# AWR2243_LC_Filtering.net
KiCad netlist of a schematic drawn in Altium Designer
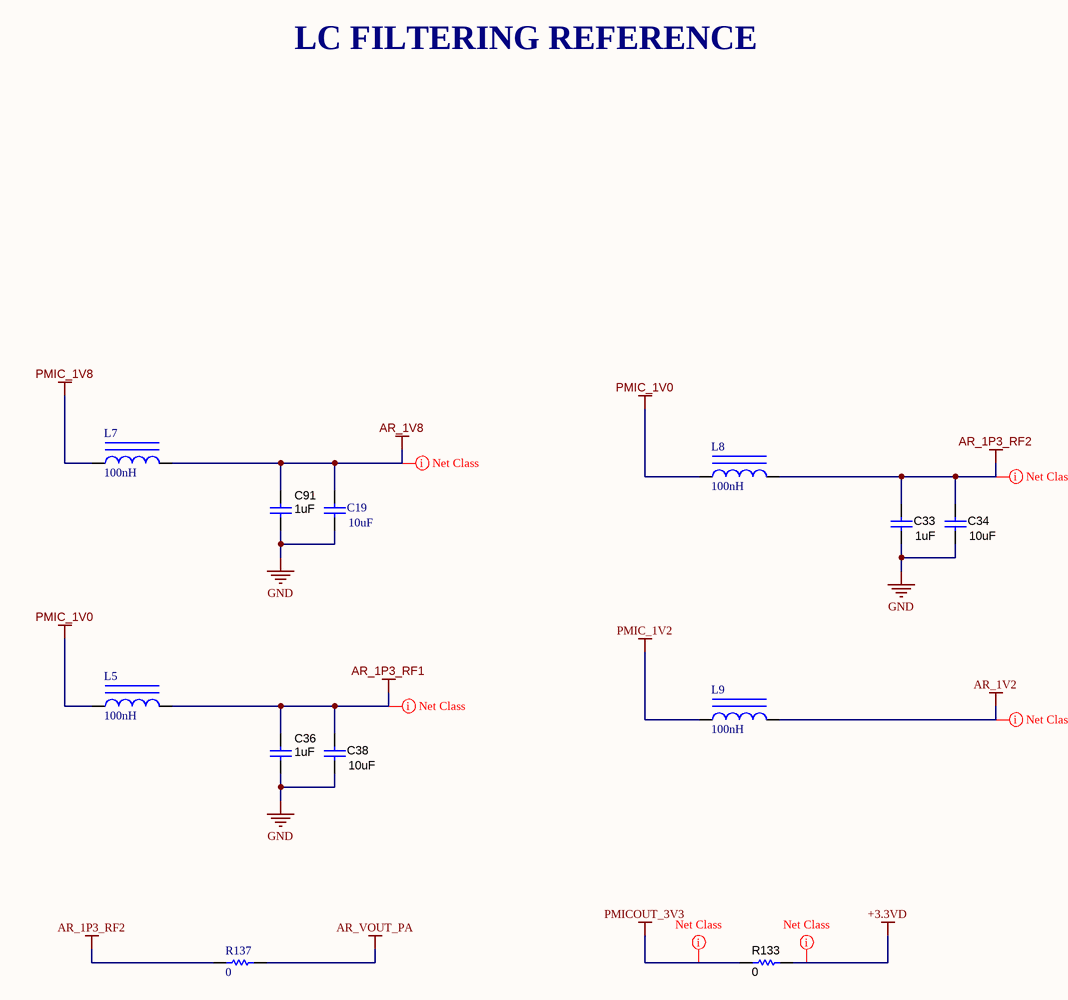
[diagram p0: AWR2243_LC_Filtering.SchDoc]

(export (version "E")
  (design (tool "Eeschema 10.0.6"))
  (components
    (comp (ref "C19")
      (value "GCM21BR71A106KE22L")
      (footprint "0805_HV")
      (description "CAP, CERM, 10 uF, 10 V, +/- 10%, X7R, 0805")
      (fields
        (field (name "MANUFACTURER") "MuRata")
        (field (name "VALUEDISPLAYED") "10uF")
        (field (name "PUBLISHER") "Texas Instruments")
      )
      (libsource (lib "Altium Vault - TI") (part "Capacitor"))
    )
    (comp (ref "C33")
      (value "GCM188R71C105KA64D")
      (footprint "0603")
      (description "CAP, CERM, 1 uF, 16 V, +/- 10%, X7R, AEC-Q200 Grade 1, 0603")
      (fields
        (field (name "MANUFACTURER") "MuRata")
        (field (name "VALUEDISPLAYED") "1uF")
        (field (name "PUBLISHER") "Texas Instruments")
      )
      (libsource (lib "Altium Vault - TI") (part "Capacitor"))
    )
    (comp (ref "C34")
      (value "GCM21BR71A106KE22L")
      (footprint "0805_HV")
      (description "CAP, CERM, 10 uF, 10 V, +/- 10%, X7R, 0805")
      (fields
        (field (name "MANUFACTURER") "MuRata")
        (field (name "VALUEDISPLAYED") "10uF")
        (field (name "PUBLISHER") "Texas Instruments")
      )
      (libsource (lib "Altium Vault - TI") (part "CMP-0008017-2"))
    )
    (comp (ref "C36")
      (value "GCM188R71C105KA64D")
      (footprint "0603")
      (description "CAP, CERM, 1 uF, 16 V, +/- 10%, X7R, AEC-Q200 Grade 1, 0603")
      (fields
        (field (name "MANUFACTURER") "MuRata")
        (field (name "VALUEDISPLAYED") "1uF")
        (field (name "PUBLISHER") "Texas Instruments")
      )
      (libsource (lib "Altium Vault - TI") (part "Capacitor"))
    )
    (comp (ref "C38")
      (value "GCM21BR71A106KE22L")
      (footprint "0805_HV")
      (description "CAP, CERM, 10 uF, 10 V, +/- 10%, X7R, 0805")
      (fields
        (field (name "MANUFACTURER") "MuRata")
        (field (name "VALUEDISPLAYED") "10uF")
        (field (name "PUBLISHER") "Texas Instruments")
      )
      (libsource (lib "Altium Vault - TI") (part "CMP-0008017-2"))
    )
    (comp (ref "C91")
      (value "GCM188R71C105KA64D")
      (footprint "0603")
      (description "CAP, CERM, 1 uF, 16 V, +/- 10%, X7R, AEC-Q200 Grade 1, 0603")
      (fields
        (field (name "MANUFACTURER") "MuRata")
        (field (name "VALUEDISPLAYED") "1uF")
        (field (name "PUBLISHER") "Texas Instruments")
      )
      (libsource (lib "Altium Vault - TI") (part "Capacitor"))
    )
    (comp (ref "L5")
      (value "NLCV32T-R10M-EFRD")
      (footprint "NLCV32")
      (description "Inductor, Wirewound, Ferrite, 100 nH, 2.85 A, 0.024 ohm, AEC-Q200 Grade 1, SMD")
      (fields (field (name "MANUFACTURER") "TDK") (field (name "VALUEDISPLAYED") "100nH"))
      (libsource (lib "Altium Vault - TI") (part "Inductor_Iron"))
    )
    (comp (ref "L7")
      (value "NLCV32T-R10M-EFRD")
      (footprint "NLCV32")
      (description "Inductor, Wirewound, Ferrite, 100 nH, 2.85 A, 0.024 ohm, AEC-Q200 Grade 1, SMD")
      (fields (field (name "MANUFACTURER") "TDK") (field (name "VALUEDISPLAYED") "100nH"))
      (libsource (lib "Altium Vault - TI") (part "Inductor_Iron"))
    )
    (comp (ref "L8")
      (value "NLCV32T-R10M-EFRD")
      (footprint "NLCV32")
      (description "Inductor, Wirewound, Ferrite, 100 nH, 2.85 A, 0.024 ohm, AEC-Q200 Grade 1, SMD")
      (fields (field (name "MANUFACTURER") "TDK") (field (name "VALUEDISPLAYED") "100nH"))
      (libsource (lib "Altium Vault - TI") (part "Inductor_Iron"))
    )
    (comp (ref "L9")
      (value "NLCV32T-R10M-EFRD")
      (footprint "NLCV32")
      (description "Inductor, Wirewound, Ferrite, 100 nH, 2.85 A, 0.024 ohm, AEC-Q200 Grade 1, SMD")
      (fields (field (name "MANUFACTURER") "TDK") (field (name "VALUEDISPLAYED") "100nH"))
      (libsource (lib "Altium Vault - TI") (part "Inductor_Iron"))
    )
    (comp (ref "R133")
      (value "MCT06030Z0000ZP500")
      (footprint "0603")
      (description "RES, 0, 5%, 0.125 W, 0603")
      (fields
        (field (name "MANUFACTURER") "Vishay/Beyschlag")
        (field (name "VALUEDISPLAYED") "0")
        (field (name "PUBLISHER") "Texas Instruments")
      )
      (libsource (lib "Altium Vault - TI") (part "Resistor"))
    )
    (comp (ref "R137")
      (value "MCT06030Z0000ZP500")
      (footprint "0603")
      (description "RES, 0, 5%, 0.125 W, 0603")
      (fields
        (field (name "MANUFACTURER") "Vishay/Beyschlag")
        (field (name "VALUEDISPLAYED") "0")
        (field (name "PUBLISHER") "Texas Instruments")
      )
      (libsource (lib "Altium Vault - TI") (part "CMP-0025884-3"))
    )
  )
  (nets
    (net (code "1") (name "+3.3VD") (class "Default")
      (node (ref "R133") (pin "2") (pinfunction "2_2") (pintype "passive"))
    )
    (net (code "2") (name "AR_1P3_RF1") (class "Default")
      (node (ref "C36") (pin "2") (pinfunction "2_2") (pintype "passive"))
      (node (ref "C38") (pin "2") (pinfunction "2_2") (pintype "passive"))
      (node (ref "L5") (pin "2") (pinfunction "2_2") (pintype "passive"))
    )
    (net (code "3") (name "AR_1P3_RF2") (class "Default")
      (node (ref "C33") (pin "2") (pinfunction "2_2") (pintype "passive"))
      (node (ref "C34") (pin "2") (pinfunction "2_2") (pintype "passive"))
      (node (ref "L8") (pin "2") (pinfunction "2_2") (pintype "passive"))
      (node (ref "R137") (pin "1") (pinfunction "1_1") (pintype "passive"))
    )
    (net (code "4") (name "AR_1V2") (class "Default")
      (node (ref "L9") (pin "2") (pinfunction "2_2") (pintype "passive"))
    )
    (net (code "5") (name "AR_1V8") (class "Default")
      (node (ref "C19") (pin "1") (pinfunction "1_1") (pintype "passive"))
      (node (ref "C91") (pin "2") (pinfunction "2_2") (pintype "passive"))
      (node (ref "L7") (pin "2") (pinfunction "2_2") (pintype "passive"))
    )
    (net (code "6") (name "AR_VOUT_PA") (class "Default")
      (node (ref "R137") (pin "2") (pinfunction "2_2") (pintype "passive"))
    )
    (net (code "7") (name "GND") (class "Default")
      (node (ref "C19") (pin "2") (pinfunction "2_2") (pintype "passive"))
      (node (ref "C33") (pin "1") (pinfunction "1_1") (pintype "passive"))
      (node (ref "C34") (pin "1") (pinfunction "1_1") (pintype "passive"))
      (node (ref "C36") (pin "1") (pinfunction "1_1") (pintype "passive"))
      (node (ref "C38") (pin "1") (pinfunction "1_1") (pintype "passive"))
      (node (ref "C91") (pin "1") (pinfunction "1_1") (pintype "passive"))
    )
    (net (code "8") (name "PMICOUT_3V3") (class "Default")
      (node (ref "R133") (pin "1") (pinfunction "1_1") (pintype "passive"))
    )
    (net (code "9") (name "PMIC_1V0") (class "Default")
      (node (ref "L5") (pin "1") (pinfunction "1_1") (pintype "passive"))
      (node (ref "L8") (pin "1") (pinfunction "1_1") (pintype "passive"))
    )
    (net (code "10") (name "PMIC_1V2") (class "Default")
      (node (ref "L9") (pin "1") (pinfunction "1_1") (pintype "passive"))
    )
    (net (code "11") (name "PMIC_1V8") (class "Default")
      (node (ref "L7") (pin "1") (pinfunction "1_1") (pintype "passive"))
    )
  )
)
